# tm4cShield_v1_0.net
KiCad netlist of a schematic drawn in EAGLE
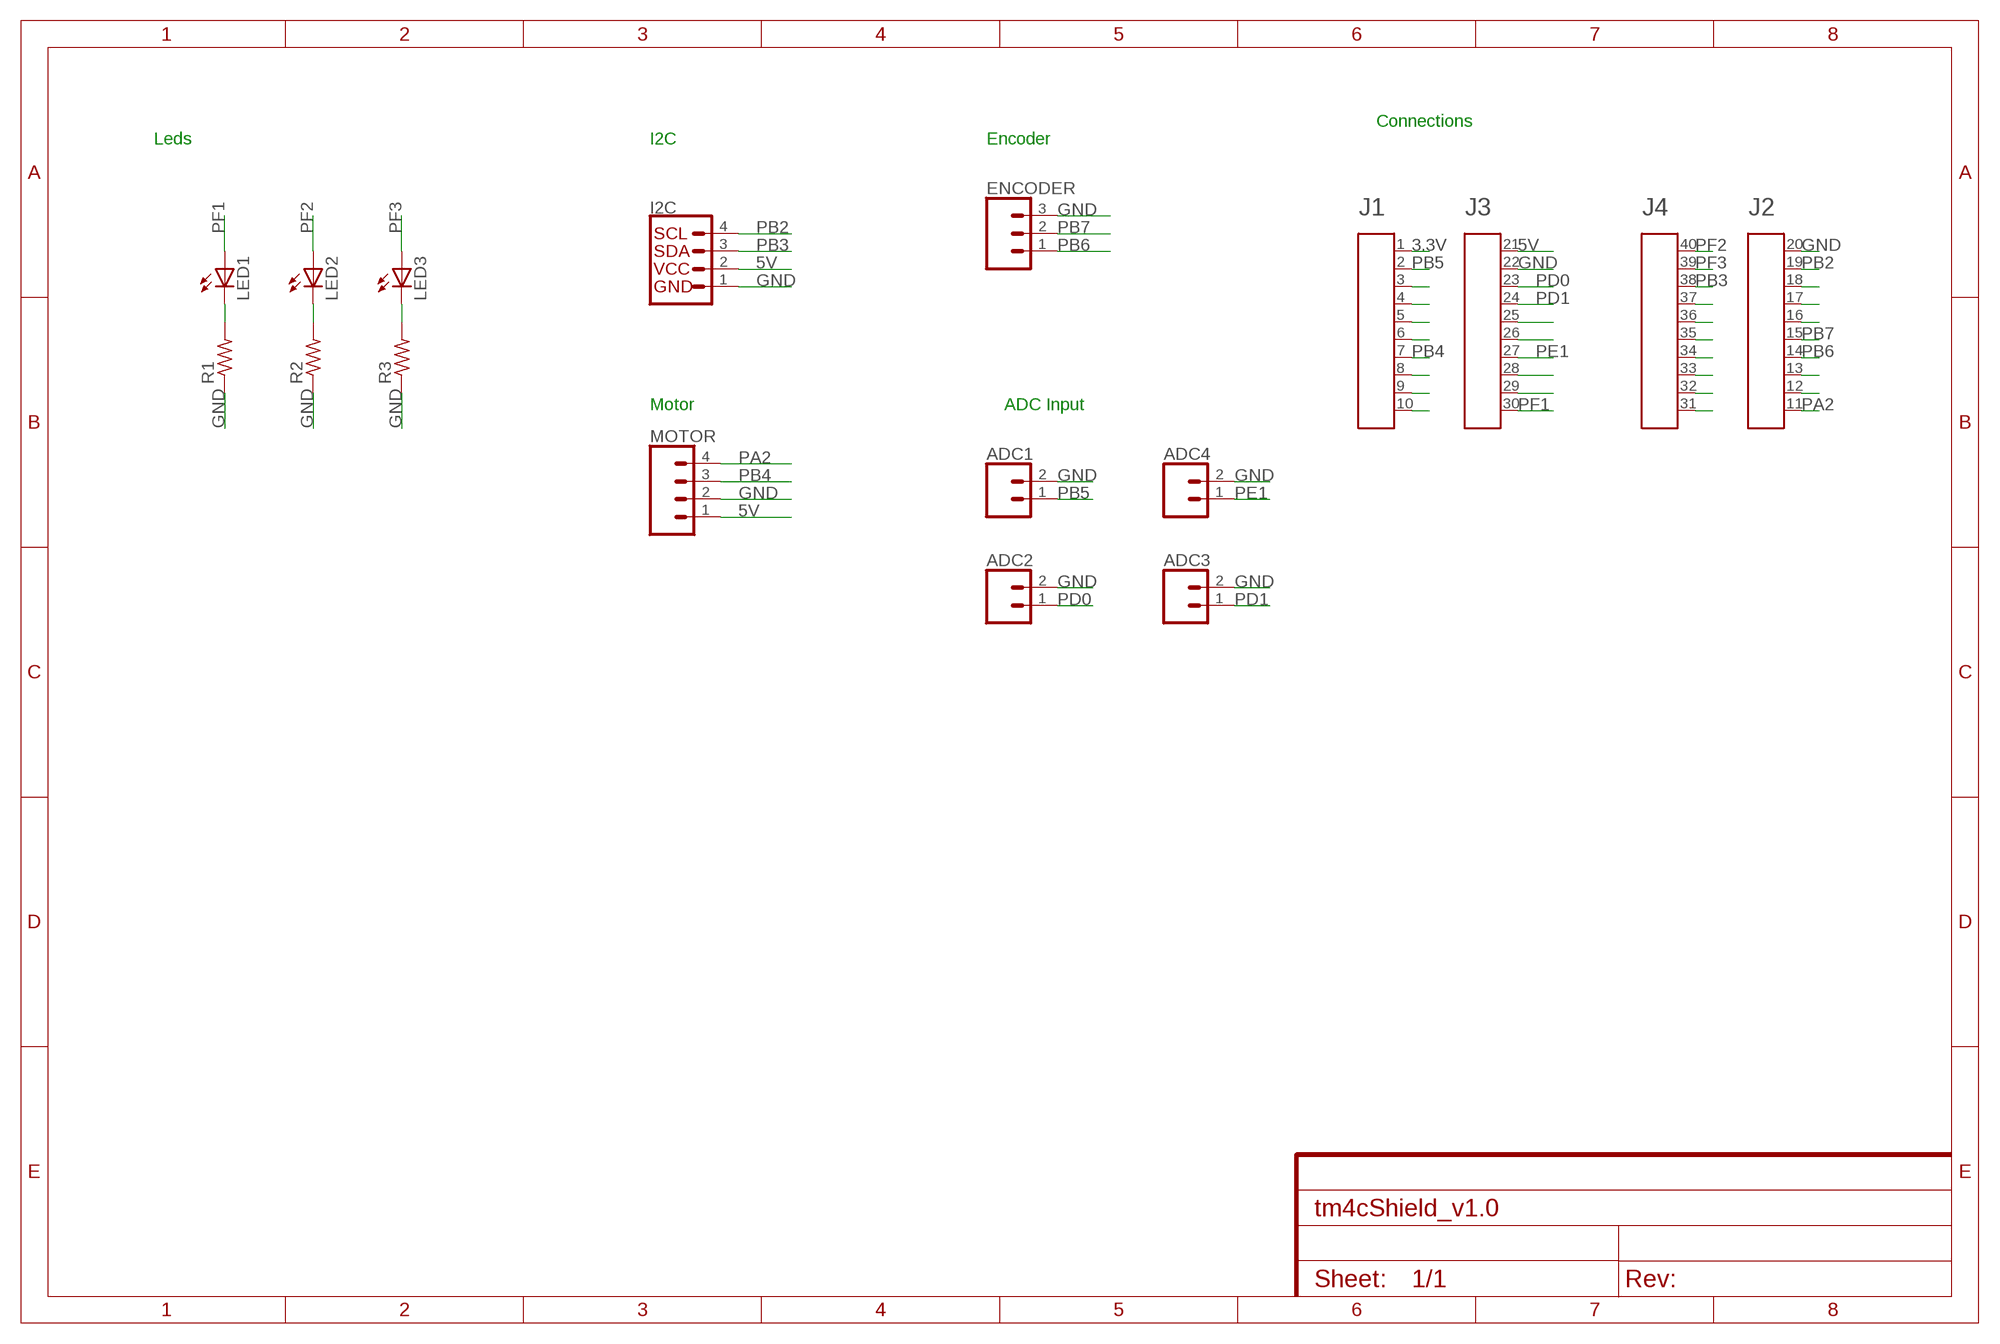
[diagram p0: schematic, sheet 1]

(export (version "E")
  (design (tool "Eeschema 10.0.6"))
  (components
    (comp (ref "A1")
      (value "HEADER4X10-BOOSTERPACK")
      (footprint "eagle-import:4X10-BOOSTERPACK")
      (libsource (lib "eagle-import") (part "HEADER4X10-BOOSTERPACK"))
    )
    (comp (ref "ADC1")
      (value "CONN_02")
      (footprint "eagle-import:1X02")
      (libsource (lib "eagle-import") (part "CONN_02"))
    )
    (comp (ref "ADC2")
      (value "CONN_02")
      (footprint "eagle-import:1X02")
      (libsource (lib "eagle-import") (part "CONN_02"))
    )
    (comp (ref "ADC3")
      (value "CONN_02")
      (footprint "eagle-import:1X02")
      (libsource (lib "eagle-import") (part "CONN_02"))
    )
    (comp (ref "ADC4")
      (value "CONN_02")
      (footprint "eagle-import:1X02")
      (libsource (lib "eagle-import") (part "CONN_02"))
    )
    (comp (ref "ENCODER")
      (value "CONN_03JST-PTH-VERT")
      (footprint "eagle-import:JST-3-PTH-VERT")
      (libsource (lib "eagle-import") (part "CONN_03JST-PTH-VERT"))
    )
    (comp (ref "I2C")
      (value "I2C_STANDARD")
      (footprint "eagle-import:1X04")
      (libsource (lib "eagle-import") (part "I2C_STANDARD"))
    )
    (comp (ref "LED1")
      (value "LED0603")
      (footprint "eagle-import:LED-0603")
      (libsource (lib "eagle-import") (part "LED0603"))
    )
    (comp (ref "LED2")
      (value "LED0603")
      (footprint "eagle-import:LED-0603")
      (libsource (lib "eagle-import") (part "LED0603"))
    )
    (comp (ref "LED3")
      (value "LED0603")
      (footprint "eagle-import:LED-0603")
      (libsource (lib "eagle-import") (part "LED0603"))
    )
    (comp (ref "MOTOR")
      (value "CONN_04JST-PTH-VERT")
      (footprint "eagle-import:JST-4-PTH-VERT")
      (libsource (lib "eagle-import") (part "CONN_04JST-PTH-VERT"))
    )
    (comp (ref "R1")
      (value "RESISTOR_0603")
      (footprint "eagle-import:RESC0603")
      (libsource (lib "eagle-import") (part "RESISTOR_0603"))
    )
    (comp (ref "R2")
      (value "RESISTOR_0603")
      (footprint "eagle-import:RESC0603")
      (libsource (lib "eagle-import") (part "RESISTOR_0603"))
    )
    (comp (ref "R3")
      (value "RESISTOR_0603")
      (footprint "eagle-import:RESC0603")
      (libsource (lib "eagle-import") (part "RESISTOR_0603"))
    )
  )
  (nets
    (net (code "1") (name "/3.3V") (class "Default")
      (node (ref "A1") (pin "1") (pinfunction "P$1_1") (pintype "bidirectional"))
    )
    (net (code "2") (name "/5V") (class "Default")
      (node (ref "A1") (pin "21") (pinfunction "P$21_21") (pintype "bidirectional"))
      (node (ref "I2C") (pin "2") (pinfunction "2_2") (pintype "power_in"))
      (node (ref "MOTOR") (pin "1") (pinfunction "1_1") (pintype "passive"))
    )
    (net (code "3") (name "/GND") (class "Default")
      (node (ref "A1") (pin "20") (pinfunction "P$20_20") (pintype "bidirectional"))
      (node (ref "A1") (pin "22") (pinfunction "P$22_22") (pintype "bidirectional"))
      (node (ref "ADC1") (pin "2") (pinfunction "2_2") (pintype "passive"))
      (node (ref "ADC2") (pin "2") (pinfunction "2_2") (pintype "passive"))
      (node (ref "ADC3") (pin "2") (pinfunction "2_2") (pintype "passive"))
      (node (ref "ADC4") (pin "2") (pinfunction "2_2") (pintype "passive"))
      (node (ref "ENCODER") (pin "3") (pinfunction "3_3") (pintype "passive"))
      (node (ref "I2C") (pin "1") (pinfunction "1_1") (pintype "power_in"))
      (node (ref "MOTOR") (pin "2") (pinfunction "2_2") (pintype "passive"))
      (node (ref "R1") (pin "1") (pinfunction "1_1") (pintype "passive"))
      (node (ref "R2") (pin "1") (pinfunction "1_1") (pintype "passive"))
      (node (ref "R3") (pin "1") (pinfunction "1_1") (pintype "passive"))
    )
    (net (code "4") (name "/PA2") (class "Default")
      (node (ref "A1") (pin "11") (pinfunction "P$11_11") (pintype "bidirectional"))
      (node (ref "MOTOR") (pin "4") (pinfunction "4_4") (pintype "passive"))
    )
    (net (code "5") (name "/PB2") (class "Default")
      (node (ref "A1") (pin "19") (pinfunction "P$19_19") (pintype "bidirectional"))
      (node (ref "I2C") (pin "4") (pinfunction "4_4") (pintype "passive"))
    )
    (net (code "6") (name "/PB3") (class "Default")
      (node (ref "A1") (pin "38") (pinfunction "P$38_38") (pintype "bidirectional"))
      (node (ref "I2C") (pin "3") (pinfunction "3_3") (pintype "passive"))
    )
    (net (code "7") (name "/PB4") (class "Default")
      (node (ref "A1") (pin "7") (pinfunction "P$7_7") (pintype "bidirectional"))
      (node (ref "MOTOR") (pin "3") (pinfunction "3_3") (pintype "passive"))
    )
    (net (code "8") (name "/PB5") (class "Default")
      (node (ref "A1") (pin "2") (pinfunction "P$2_2") (pintype "bidirectional"))
      (node (ref "ADC1") (pin "1") (pinfunction "1_1") (pintype "passive"))
    )
    (net (code "9") (name "/PB6") (class "Default")
      (node (ref "A1") (pin "14") (pinfunction "P$14_14") (pintype "bidirectional"))
      (node (ref "ENCODER") (pin "1") (pinfunction "1_1") (pintype "passive"))
    )
    (net (code "10") (name "/PB7") (class "Default")
      (node (ref "A1") (pin "15") (pinfunction "P$15_15") (pintype "bidirectional"))
      (node (ref "ENCODER") (pin "2") (pinfunction "2_2") (pintype "passive"))
    )
    (net (code "11") (name "/PD0") (class "Default")
      (node (ref "A1") (pin "23") (pinfunction "P$23_23") (pintype "bidirectional"))
      (node (ref "ADC2") (pin "1") (pinfunction "1_1") (pintype "passive"))
    )
    (net (code "12") (name "/PD1") (class "Default")
      (node (ref "A1") (pin "24") (pinfunction "P$24_24") (pintype "bidirectional"))
      (node (ref "ADC3") (pin "1") (pinfunction "1_1") (pintype "passive"))
    )
    (net (code "13") (name "/PE1") (class "Default")
      (node (ref "A1") (pin "27") (pinfunction "P$27_27") (pintype "bidirectional"))
      (node (ref "ADC4") (pin "1") (pinfunction "1_1") (pintype "passive"))
    )
    (net (code "14") (name "/PF1") (class "Default")
      (node (ref "A1") (pin "30") (pinfunction "P$30_30") (pintype "bidirectional"))
      (node (ref "LED1") (pin "A") (pinfunction "A_A") (pintype "passive"))
    )
    (net (code "15") (name "/PF2") (class "Default")
      (node (ref "A1") (pin "40") (pinfunction "P$40_40") (pintype "bidirectional"))
      (node (ref "LED2") (pin "A") (pinfunction "A_A") (pintype "passive"))
    )
    (net (code "16") (name "/PF3") (class "Default")
      (node (ref "A1") (pin "39") (pinfunction "P$39_39") (pintype "bidirectional"))
      (node (ref "LED3") (pin "A") (pinfunction "A_A") (pintype "passive"))
    )
    (net (code "17") (name "Net-(LED1-PadC)") (class "Default")
      (node (ref "LED1") (pin "C") (pinfunction "C_C") (pintype "passive"))
      (node (ref "R1") (pin "2") (pinfunction "2_2") (pintype "passive"))
    )
    (net (code "18") (name "Net-(LED2-PadC)") (class "Default")
      (node (ref "LED2") (pin "C") (pinfunction "C_C") (pintype "passive"))
      (node (ref "R2") (pin "2") (pinfunction "2_2") (pintype "passive"))
    )
    (net (code "19") (name "Net-(LED3-PadC)") (class "Default")
      (node (ref "LED3") (pin "C") (pinfunction "C_C") (pintype "passive"))
      (node (ref "R3") (pin "2") (pinfunction "2_2") (pintype "passive"))
    )
    (net (code "20") (name "unconnected-(A1-P$3-Pad3)") (class "Default")
      (node (ref "A1") (pin "3") (pinfunction "P$3_3") (pintype "bidirectional"))
    )
    (net (code "21") (name "unconnected-(A1-P$4-Pad4)") (class "Default")
      (node (ref "A1") (pin "4") (pinfunction "P$4_4") (pintype "bidirectional"))
    )
    (net (code "22") (name "unconnected-(A1-P$5-Pad5)") (class "Default")
      (node (ref "A1") (pin "5") (pinfunction "P$5_5") (pintype "bidirectional"))
    )
    (net (code "23") (name "unconnected-(A1-P$6-Pad6)") (class "Default")
      (node (ref "A1") (pin "6") (pinfunction "P$6_6") (pintype "bidirectional"))
    )
    (net (code "24") (name "unconnected-(A1-P$8-Pad8)") (class "Default")
      (node (ref "A1") (pin "8") (pinfunction "P$8_8") (pintype "bidirectional"))
    )
    (net (code "25") (name "unconnected-(A1-P$9-Pad9)") (class "Default")
      (node (ref "A1") (pin "9") (pinfunction "P$9_9") (pintype "bidirectional"))
    )
    (net (code "26") (name "unconnected-(A1-P$10-Pad10)") (class "Default")
      (node (ref "A1") (pin "10") (pinfunction "P$10_10") (pintype "bidirectional"))
    )
    (net (code "27") (name "unconnected-(A1-P$12-Pad12)") (class "Default")
      (node (ref "A1") (pin "12") (pinfunction "P$12_12") (pintype "bidirectional"))
    )
    (net (code "28") (name "unconnected-(A1-P$13-Pad13)") (class "Default")
      (node (ref "A1") (pin "13") (pinfunction "P$13_13") (pintype "bidirectional"))
    )
    (net (code "29") (name "unconnected-(A1-P$16-Pad16)") (class "Default")
      (node (ref "A1") (pin "16") (pinfunction "P$16_16") (pintype "bidirectional"))
    )
    (net (code "30") (name "unconnected-(A1-P$17-Pad17)") (class "Default")
      (node (ref "A1") (pin "17") (pinfunction "P$17_17") (pintype "bidirectional"))
    )
    (net (code "31") (name "unconnected-(A1-P$18-Pad18)") (class "Default")
      (node (ref "A1") (pin "18") (pinfunction "P$18_18") (pintype "bidirectional"))
    )
    (net (code "32") (name "unconnected-(A1-P$25-Pad25)") (class "Default")
      (node (ref "A1") (pin "25") (pinfunction "P$25_25") (pintype "bidirectional"))
    )
    (net (code "33") (name "unconnected-(A1-P$26-Pad26)") (class "Default")
      (node (ref "A1") (pin "26") (pinfunction "P$26_26") (pintype "bidirectional"))
    )
    (net (code "34") (name "unconnected-(A1-P$28-Pad28)") (class "Default")
      (node (ref "A1") (pin "28") (pinfunction "P$28_28") (pintype "bidirectional"))
    )
    (net (code "35") (name "unconnected-(A1-P$29-Pad29)") (class "Default")
      (node (ref "A1") (pin "29") (pinfunction "P$29_29") (pintype "bidirectional"))
    )
    (net (code "36") (name "unconnected-(A1-P$31-Pad31)") (class "Default")
      (node (ref "A1") (pin "31") (pinfunction "P$31_31") (pintype "bidirectional"))
    )
    (net (code "37") (name "unconnected-(A1-P$32-Pad32)") (class "Default")
      (node (ref "A1") (pin "32") (pinfunction "P$32_32") (pintype "bidirectional"))
    )
    (net (code "38") (name "unconnected-(A1-P$33-Pad33)") (class "Default")
      (node (ref "A1") (pin "33") (pinfunction "P$33_33") (pintype "bidirectional"))
    )
    (net (code "39") (name "unconnected-(A1-P$34-Pad34)") (class "Default")
      (node (ref "A1") (pin "34") (pinfunction "P$34_34") (pintype "bidirectional"))
    )
    (net (code "40") (name "unconnected-(A1-P$35-Pad35)") (class "Default")
      (node (ref "A1") (pin "35") (pinfunction "P$35_35") (pintype "bidirectional"))
    )
    (net (code "41") (name "unconnected-(A1-P$36-Pad36)") (class "Default")
      (node (ref "A1") (pin "36") (pinfunction "P$36_36") (pintype "bidirectional"))
    )
    (net (code "42") (name "unconnected-(A1-P$37-Pad37)") (class "Default")
      (node (ref "A1") (pin "37") (pinfunction "P$37_37") (pintype "bidirectional"))
    )
  )
)
